# Footpedal-Wiring.net
KiCad netlist of a schematic drawn in Altium Designer
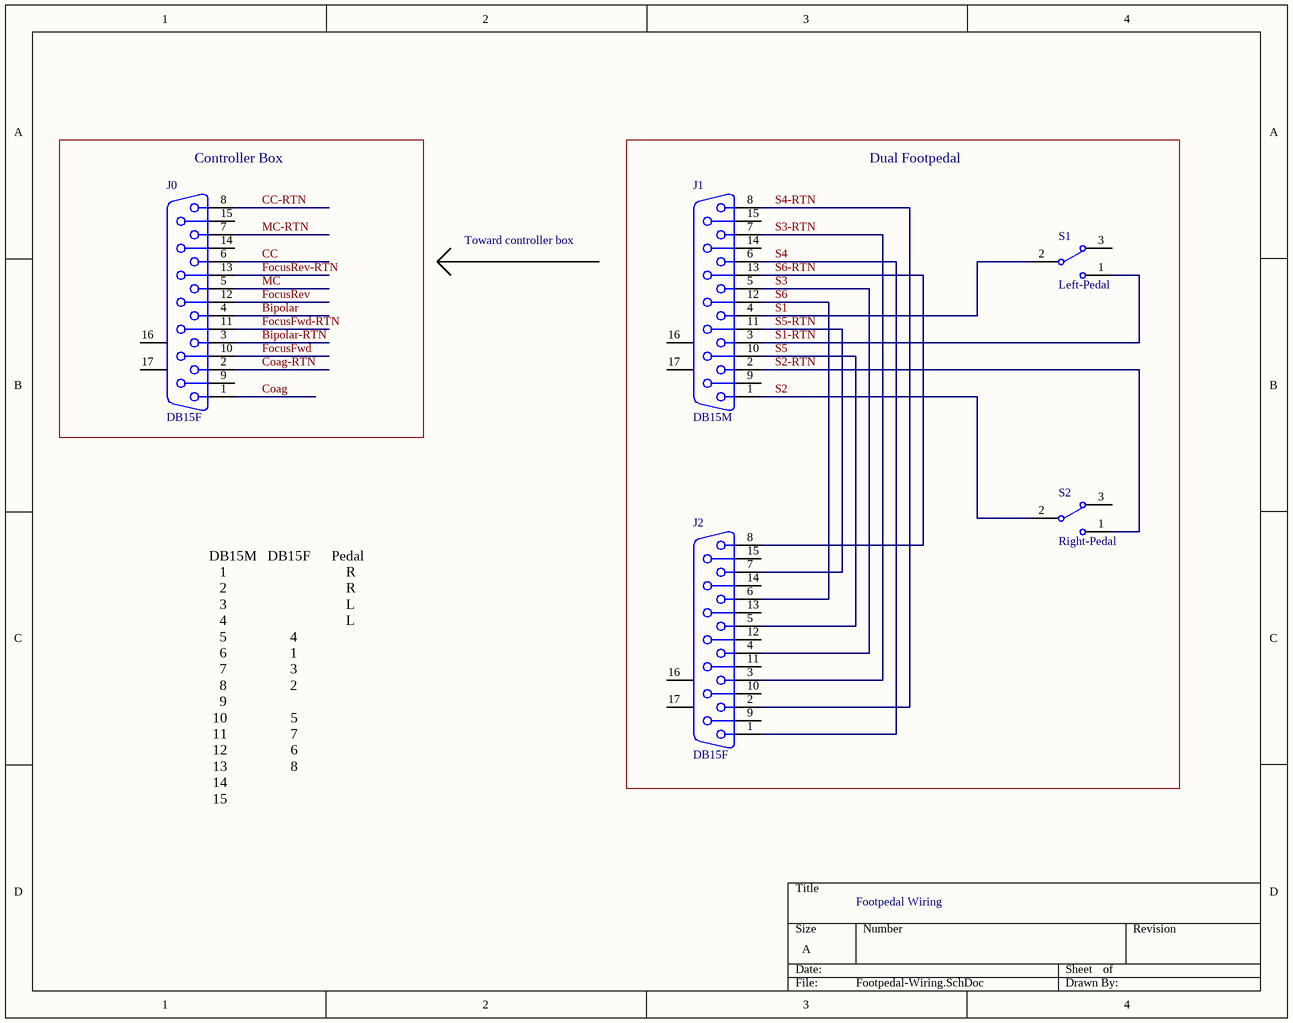
[diagram p0: Footpedal-Wiring.SchDoc]

(export (version "E")
  (design (tool "Eeschema 10.0.6"))
  (components
    (comp (ref "J0")
      (value "DB15F")
      (footprint "DSUB1.385-2H15")
      (description "Receptacle Assembly, 15 Position, Right Angle")
      (fields (field (name "PUBLISHER") "Altium Limited"))
      (libsource (lib "Miscellaneous Connectors") (part "D Connector 15"))
    )
    (comp (ref "J1")
      (value "DB15M")
      (footprint "DSUB1.385-2H15")
      (description "Receptacle Assembly, 15 Position, Right Angle")
      (fields (field (name "PUBLISHER") "Altium Limited"))
      (libsource (lib "Miscellaneous Connectors") (part "D Connector 15"))
    )
    (comp (ref "J2")
      (value "DB15F")
      (footprint "DSUB1.385-2H15")
      (description "Receptacle Assembly, 15 Position, Right Angle")
      (fields (field (name "PUBLISHER") "Altium Limited"))
      (libsource (lib "Miscellaneous Connectors") (part "D Connector 15"))
    )
    (comp (ref "S1")
      (value "Left-Pedal")
      (footprint "TL36WW15050")
      (description "SPDT Subminiature Toggle Switch, Right Angle Mounting, Vertical Actuation")
      (fields (field (name "PUBLISHER") "Altium Limited"))
      (libsource (lib "Miscellaneous Devices") (part "SW-SPDT"))
    )
    (comp (ref "S2")
      (value "Right-Pedal")
      (footprint "TL36WW15050")
      (description "SPDT Subminiature Toggle Switch, Right Angle Mounting, Vertical Actuation")
      (fields (field (name "PUBLISHER") "Altium Limited"))
      (libsource (lib "Miscellaneous Devices") (part "SW-SPDT"))
    )
  )
  (nets
    (net (code "1") (name "/Bipolar") (class "Default")
      (node (ref "J0") (pin "4") (pinfunction "4_4") (pintype "passive"))
    )
    (net (code "2") (name "/Bipolar-RTN") (class "Default")
      (node (ref "J0") (pin "3") (pinfunction "3_3") (pintype "passive"))
    )
    (net (code "3") (name "/CC") (class "Default")
      (node (ref "J0") (pin "6") (pinfunction "6_6") (pintype "passive"))
    )
    (net (code "4") (name "/CC-RTN") (class "Default")
      (node (ref "J0") (pin "8") (pinfunction "8_8") (pintype "passive"))
    )
    (net (code "5") (name "/Coag") (class "Default")
      (node (ref "J0") (pin "1") (pinfunction "1_1") (pintype "passive"))
    )
    (net (code "6") (name "/Coag-RTN") (class "Default")
      (node (ref "J0") (pin "2") (pinfunction "2_2") (pintype "passive"))
    )
    (net (code "7") (name "/FocusFwd") (class "Default")
      (node (ref "J0") (pin "10") (pinfunction "10_10") (pintype "passive"))
    )
    (net (code "8") (name "/FocusFwd-RTN") (class "Default")
      (node (ref "J0") (pin "11") (pinfunction "11_11") (pintype "passive"))
    )
    (net (code "9") (name "/FocusRev") (class "Default")
      (node (ref "J0") (pin "12") (pinfunction "12_12") (pintype "passive"))
    )
    (net (code "10") (name "/FocusRev-RTN") (class "Default")
      (node (ref "J0") (pin "13") (pinfunction "13_13") (pintype "passive"))
    )
    (net (code "11") (name "/MC") (class "Default")
      (node (ref "J0") (pin "5") (pinfunction "5_5") (pintype "passive"))
    )
    (net (code "12") (name "/MC-RTN") (class "Default")
      (node (ref "J0") (pin "7") (pinfunction "7_7") (pintype "passive"))
    )
    (net (code "13") (name "/S1") (class "Default")
      (node (ref "J1") (pin "4") (pinfunction "4_4") (pintype "passive"))
      (node (ref "S1") (pin "2") (pinfunction "2_2") (pintype "passive"))
    )
    (net (code "14") (name "/S1-RTN") (class "Default")
      (node (ref "J1") (pin "3") (pinfunction "3_3") (pintype "passive"))
      (node (ref "S1") (pin "1") (pinfunction "1_1") (pintype "passive"))
    )
    (net (code "15") (name "/S2") (class "Default")
      (node (ref "J1") (pin "1") (pinfunction "1_1") (pintype "passive"))
      (node (ref "S2") (pin "2") (pinfunction "2_2") (pintype "passive"))
    )
    (net (code "16") (name "/S2-RTN") (class "Default")
      (node (ref "J1") (pin "2") (pinfunction "2_2") (pintype "passive"))
      (node (ref "S2") (pin "1") (pinfunction "1_1") (pintype "passive"))
    )
    (net (code "17") (name "/S3") (class "Default")
      (node (ref "J1") (pin "5") (pinfunction "5_5") (pintype "passive"))
      (node (ref "J2") (pin "4") (pinfunction "4_4") (pintype "passive"))
    )
    (net (code "18") (name "/S3-RTN") (class "Default")
      (node (ref "J1") (pin "7") (pinfunction "7_7") (pintype "passive"))
      (node (ref "J2") (pin "3") (pinfunction "3_3") (pintype "passive"))
    )
    (net (code "19") (name "/S4") (class "Default")
      (node (ref "J1") (pin "6") (pinfunction "6_6") (pintype "passive"))
      (node (ref "J2") (pin "1") (pinfunction "1_1") (pintype "passive"))
    )
    (net (code "20") (name "/S4-RTN") (class "Default")
      (node (ref "J1") (pin "8") (pinfunction "8_8") (pintype "passive"))
      (node (ref "J2") (pin "2") (pinfunction "2_2") (pintype "passive"))
    )
    (net (code "21") (name "/S5") (class "Default")
      (node (ref "J1") (pin "10") (pinfunction "10_10") (pintype "passive"))
      (node (ref "J2") (pin "5") (pinfunction "5_5") (pintype "passive"))
    )
    (net (code "22") (name "/S5-RTN") (class "Default")
      (node (ref "J1") (pin "11") (pinfunction "11_11") (pintype "passive"))
      (node (ref "J2") (pin "7") (pinfunction "7_7") (pintype "passive"))
    )
    (net (code "23") (name "/S6") (class "Default")
      (node (ref "J1") (pin "12") (pinfunction "12_12") (pintype "passive"))
      (node (ref "J2") (pin "6") (pinfunction "6_6") (pintype "passive"))
    )
    (net (code "24") (name "/S6-RTN") (class "Default")
      (node (ref "J1") (pin "13") (pinfunction "13_13") (pintype "passive"))
      (node (ref "J2") (pin "8") (pinfunction "8_8") (pintype "passive"))
    )
    (net (code "25") (name "unconnected-(J0-MH1-Pad16)") (class "Default")
      (node (ref "J0") (pin "16") (pinfunction "MH1_16") (pintype "passive"))
    )
    (net (code "26") (name "unconnected-(J0-MH2-Pad17)") (class "Default")
      (node (ref "J0") (pin "17") (pinfunction "MH2_17") (pintype "passive"))
    )
    (net (code "27") (name "unconnected-(J0-Pad9)") (class "Default")
      (node (ref "J0") (pin "9") (pinfunction "9_9") (pintype "passive"))
    )
    (net (code "28") (name "unconnected-(J0-Pad14)") (class "Default")
      (node (ref "J0") (pin "14") (pinfunction "14_14") (pintype "passive"))
    )
    (net (code "29") (name "unconnected-(J0-Pad15)") (class "Default")
      (node (ref "J0") (pin "15") (pinfunction "15_15") (pintype "passive"))
    )
    (net (code "30") (name "unconnected-(J1-MH1-Pad16)") (class "Default")
      (node (ref "J1") (pin "16") (pinfunction "MH1_16") (pintype "passive"))
    )
    (net (code "31") (name "unconnected-(J1-MH2-Pad17)") (class "Default")
      (node (ref "J1") (pin "17") (pinfunction "MH2_17") (pintype "passive"))
    )
    (net (code "32") (name "unconnected-(J1-Pad9)") (class "Default")
      (node (ref "J1") (pin "9") (pinfunction "9_9") (pintype "passive"))
    )
    (net (code "33") (name "unconnected-(J1-Pad14)") (class "Default")
      (node (ref "J1") (pin "14") (pinfunction "14_14") (pintype "passive"))
    )
    (net (code "34") (name "unconnected-(J1-Pad15)") (class "Default")
      (node (ref "J1") (pin "15") (pinfunction "15_15") (pintype "passive"))
    )
    (net (code "35") (name "unconnected-(J2-MH1-Pad16)") (class "Default")
      (node (ref "J2") (pin "16") (pinfunction "MH1_16") (pintype "passive"))
    )
    (net (code "36") (name "unconnected-(J2-MH2-Pad17)") (class "Default")
      (node (ref "J2") (pin "17") (pinfunction "MH2_17") (pintype "passive"))
    )
    (net (code "37") (name "unconnected-(J2-Pad9)") (class "Default")
      (node (ref "J2") (pin "9") (pinfunction "9_9") (pintype "passive"))
    )
    (net (code "38") (name "unconnected-(J2-Pad10)") (class "Default")
      (node (ref "J2") (pin "10") (pinfunction "10_10") (pintype "passive"))
    )
    (net (code "39") (name "unconnected-(J2-Pad11)") (class "Default")
      (node (ref "J2") (pin "11") (pinfunction "11_11") (pintype "passive"))
    )
    (net (code "40") (name "unconnected-(J2-Pad12)") (class "Default")
      (node (ref "J2") (pin "12") (pinfunction "12_12") (pintype "passive"))
    )
    (net (code "41") (name "unconnected-(J2-Pad13)") (class "Default")
      (node (ref "J2") (pin "13") (pinfunction "13_13") (pintype "passive"))
    )
    (net (code "42") (name "unconnected-(J2-Pad14)") (class "Default")
      (node (ref "J2") (pin "14") (pinfunction "14_14") (pintype "passive"))
    )
    (net (code "43") (name "unconnected-(J2-Pad15)") (class "Default")
      (node (ref "J2") (pin "15") (pinfunction "15_15") (pintype "passive"))
    )
    (net (code "44") (name "unconnected-(S1-Pad3)") (class "Default")
      (node (ref "S1") (pin "3") (pinfunction "3_3") (pintype "passive"))
    )
    (net (code "45") (name "unconnected-(S2-Pad3)") (class "Default")
      (node (ref "S2") (pin "3") (pinfunction "3_3") (pintype "passive"))
    )
  )
)
